# MCU_V3.net
KiCad netlist of a schematic drawn in EAGLE
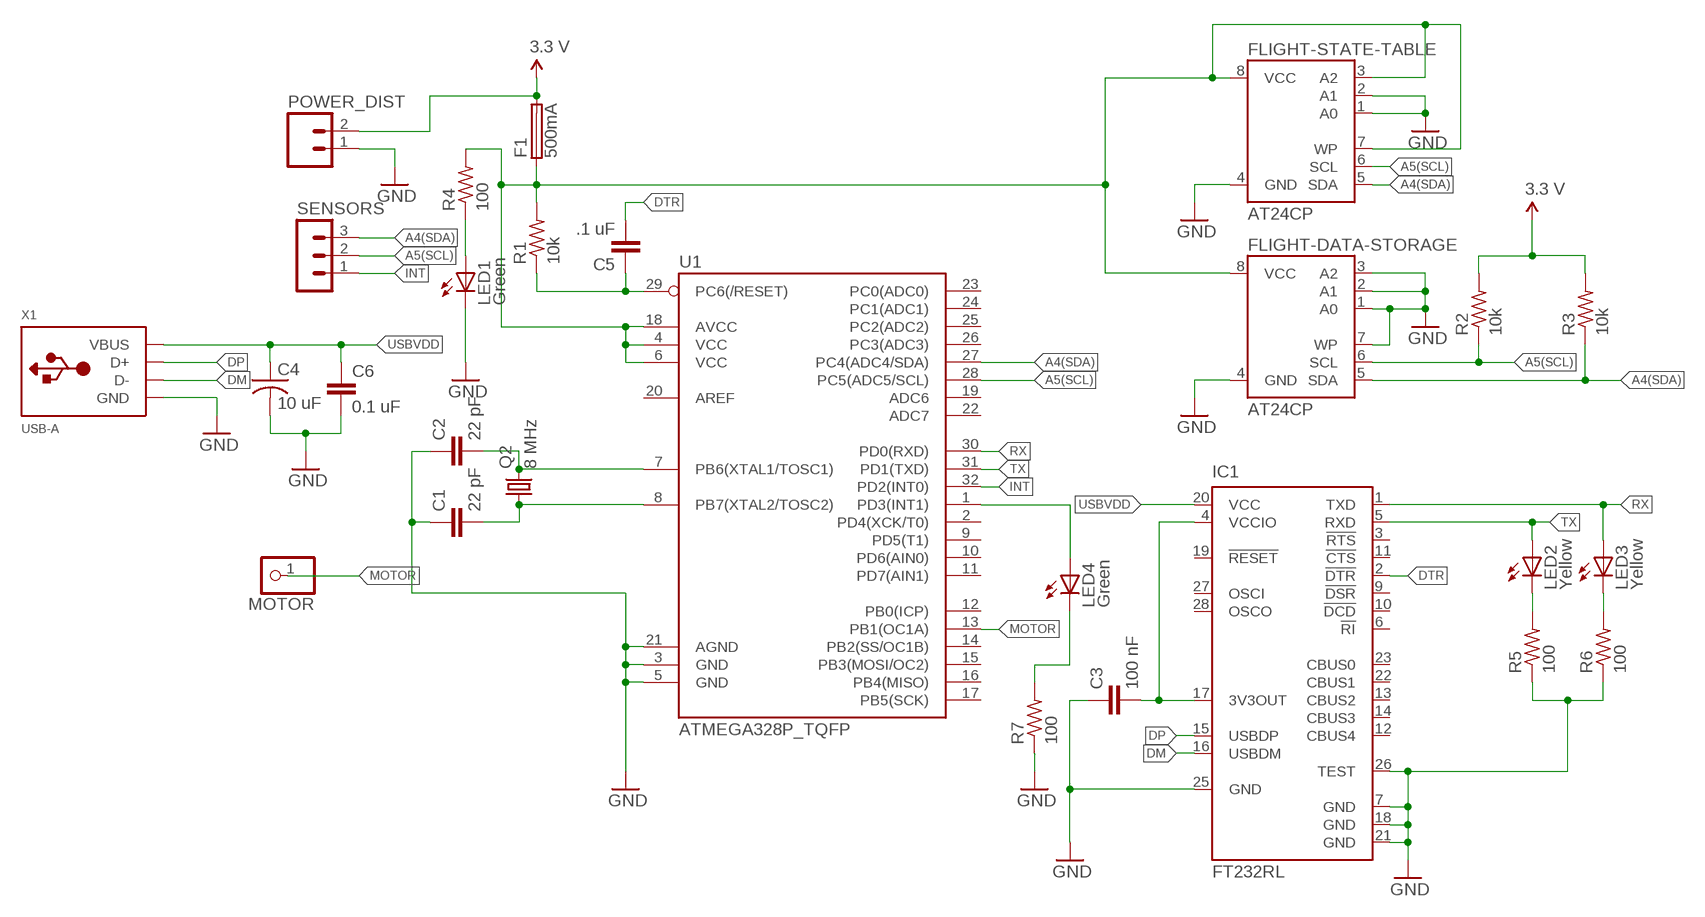
[diagram p0: schematic, sheet 1]

(export (version "E")
  (design (tool "Eeschema 10.0.6"))
  (components
    (comp (ref "C1")
      (value "22 pF")
      (footprint "eagle-import:C2.5-3")
      (libsource (lib "eagle-import") (part "C2,5-3"))
    )
    (comp (ref "C2")
      (value "22 pF")
      (footprint "eagle-import:C2.5-3")
      (libsource (lib "eagle-import") (part "C2,5-3"))
    )
    (comp (ref "C3")
      (value "100 nF")
      (footprint "eagle-import:C2.5-3")
      (libsource (lib "eagle-import") (part "C2,5-3"))
    )
    (comp (ref "C4")
      (value "10 uF")
      (footprint "eagle-import:C025-024X044")
      (libsource (lib "eagle-import") (part "C-US025-024X044"))
    )
    (comp (ref "C5")
      (value ".1 uF")
      (footprint "eagle-import:C2.5-3")
      (libsource (lib "eagle-import") (part "C2,5-3"))
    )
    (comp (ref "C6")
      (value "0.1 uF")
      (footprint "eagle-import:C2.5-3")
      (libsource (lib "eagle-import") (part "C2,5-3"))
    )
    (comp (ref "F1")
      (value "500mA")
      (footprint "eagle-import:PICOFUSE")
      (libsource (lib "eagle-import") (part "PICOFUSE"))
    )
    (comp (ref "FLIGHT-DATA-STORAGE")
      (value "AT24CP")
      (footprint "eagle-import:DIL08")
      (fields (field (name "MPN") "AT24C1024BW-SH-B"))
      (libsource (lib "eagle-import") (part "AT24CP"))
    )
    (comp (ref "FLIGHT-STATE-TABLE")
      (value "AT24CP")
      (footprint "eagle-import:DIL08")
      (fields (field (name "MPN") "AT24C1024BW-SH-B"))
      (libsource (lib "eagle-import") (part "AT24CP"))
    )
    (comp (ref "IC1")
      (value "FT232RL")
      (footprint "eagle-import:SSOP28")
      (libsource (lib "eagle-import") (part "FT232RL"))
    )
    (comp (ref "LED1")
      (value "Green")
      (footprint "eagle-import:LED_SML0603")
      (libsource (lib "eagle-import") (part "LED_ESML0603"))
    )
    (comp (ref "LED2")
      (value "Yellow")
      (footprint "eagle-import:LED_SML0603")
      (libsource (lib "eagle-import") (part "LED_ESML0603"))
    )
    (comp (ref "LED3")
      (value "Yellow")
      (footprint "eagle-import:LED_SML0603")
      (libsource (lib "eagle-import") (part "LED_ESML0603"))
    )
    (comp (ref "LED4")
      (value "Green")
      (footprint "eagle-import:LED_SML0603")
      (libsource (lib "eagle-import") (part "LED_ESML0603"))
    )
    (comp (ref "MOTOR")
      (value "PINHD-1X1")
      (footprint "eagle-import:1X01")
      (libsource (lib "eagle-import") (part "PINHD-1X1"))
    )
    (comp (ref "POWER_DIST")
      (value "M02PTH")
      (footprint "eagle-import:1X02")
      (libsource (lib "eagle-import") (part "M02PTH"))
    )
    (comp (ref "Q2")
      (value "8 MHz")
      (footprint "eagle-import:HC49_S")
      (libsource (lib "eagle-import") (part "CRYSTALHC49S"))
    )
    (comp (ref "R1")
      (value "10k")
      (footprint "eagle-import:R0805")
      (libsource (lib "eagle-import") (part "R-US_R0805"))
    )
    (comp (ref "R2")
      (value "10k")
      (footprint "eagle-import:R0805")
      (libsource (lib "eagle-import") (part "R-US_R0805"))
    )
    (comp (ref "R3")
      (value "10k")
      (footprint "eagle-import:R0805")
      (libsource (lib "eagle-import") (part "R-US_R0805"))
    )
    (comp (ref "R4")
      (value "100")
      (footprint "eagle-import:R0805")
      (libsource (lib "eagle-import") (part "R-US_R0805"))
    )
    (comp (ref "R5")
      (value "100")
      (footprint "eagle-import:R0805")
      (libsource (lib "eagle-import") (part "R-US_R0805"))
    )
    (comp (ref "R6")
      (value "100")
      (footprint "eagle-import:R0805")
      (libsource (lib "eagle-import") (part "R-US_R0805"))
    )
    (comp (ref "R7")
      (value "100")
      (footprint "eagle-import:R0805")
      (libsource (lib "eagle-import") (part "R-US_R0805"))
    )
    (comp (ref "SENSORS")
      (value "MA03-1")
      (footprint "eagle-import:MA03-1")
      (libsource (lib "eagle-import") (part "MA03-1"))
    )
    (comp (ref "U1")
      (value "ATMEGA328P_TQFP")
      (footprint "eagle-import:TQFP32-08")
      (libsource (lib "eagle-import") (part "ATMEGA328P_TQFP"))
    )
    (comp (ref "X1")
      (value "USB-A")
      (footprint "eagle-import:MOLEX_480371000")
      (libsource (lib "eagle-import") (part "USB-A"))
    )
  )
  (nets
    (net (code "1") (name "3.3 V") (class "Default")
      (node (ref "F1") (pin "2") (pinfunction "2_2") (pintype "passive"))
      (node (ref "POWER_DIST") (pin "2") (pinfunction "2_2") (pintype "passive"))
      (node (ref "R2") (pin "2") (pinfunction "2_2") (pintype "passive"))
      (node (ref "R3") (pin "2") (pinfunction "2_2") (pintype "passive"))
    )
    (net (code "2") (name "A4(SDA)") (class "Default")
      (node (ref "FLIGHT-DATA-STORAGE") (pin "5") (pinfunction "SDA_5") (pintype "bidirectional"))
      (node (ref "FLIGHT-STATE-TABLE") (pin "5") (pinfunction "SDA_5") (pintype "bidirectional"))
      (node (ref "R3") (pin "1") (pinfunction "1_1") (pintype "passive"))
      (node (ref "SENSORS") (pin "3") (pinfunction "3_3") (pintype "passive"))
      (node (ref "U1") (pin "27") (pinfunction "PC4(ADC4/SDA)_27") (pintype "bidirectional"))
    )
    (net (code "3") (name "A5(SCL)") (class "Default")
      (node (ref "FLIGHT-DATA-STORAGE") (pin "6") (pinfunction "SCL_6") (pintype "bidirectional"))
      (node (ref "FLIGHT-STATE-TABLE") (pin "6") (pinfunction "SCL_6") (pintype "bidirectional"))
      (node (ref "R2") (pin "1") (pinfunction "1_1") (pintype "passive"))
      (node (ref "SENSORS") (pin "2") (pinfunction "2_2") (pintype "passive"))
      (node (ref "U1") (pin "28") (pinfunction "PC5(ADC5/SCL)_28") (pintype "bidirectional"))
    )
    (net (code "4") (name "DM") (class "Default")
      (node (ref "IC1") (pin "16") (pinfunction "USBDM_16") (pintype "bidirectional"))
      (node (ref "X1") (pin "2") (pinfunction "D-_2") (pintype "bidirectional"))
    )
    (net (code "5") (name "DP") (class "Default")
      (node (ref "IC1") (pin "15") (pinfunction "USBDP_15") (pintype "bidirectional"))
      (node (ref "X1") (pin "3") (pinfunction "D+_3") (pintype "bidirectional"))
    )
    (net (code "6") (name "DTR") (class "Default")
      (node (ref "C5") (pin "2") (pinfunction "2_2") (pintype "passive"))
      (node (ref "IC1") (pin "2") (pinfunction "~{DTR}_2") (pintype "output"))
    )
    (net (code "7") (name "GND") (class "Default")
      (node (ref "C1") (pin "1") (pinfunction "1_1") (pintype "passive"))
      (node (ref "C2") (pin "1") (pinfunction "1_1") (pintype "passive"))
      (node (ref "C3") (pin "1") (pinfunction "1_1") (pintype "passive"))
      (node (ref "C4") (pin "2") (pinfunction "2_2") (pintype "passive"))
      (node (ref "C6") (pin "2") (pinfunction "2_2") (pintype "passive"))
      (node (ref "FLIGHT-DATA-STORAGE") (pin "1") (pinfunction "A0_1") (pintype "input"))
      (node (ref "FLIGHT-DATA-STORAGE") (pin "2") (pinfunction "A1_2") (pintype "input"))
      (node (ref "FLIGHT-DATA-STORAGE") (pin "3") (pinfunction "A2_3") (pintype "input"))
      (node (ref "FLIGHT-DATA-STORAGE") (pin "4") (pinfunction "GND_4") (pintype "power_in"))
      (node (ref "FLIGHT-DATA-STORAGE") (pin "7") (pinfunction "WP_7") (pintype "input"))
      (node (ref "FLIGHT-STATE-TABLE") (pin "1") (pinfunction "A0_1") (pintype "input"))
      (node (ref "FLIGHT-STATE-TABLE") (pin "2") (pinfunction "A1_2") (pintype "input"))
      (node (ref "FLIGHT-STATE-TABLE") (pin "4") (pinfunction "GND_4") (pintype "power_in"))
      (node (ref "IC1") (pin "18") (pinfunction "GND_18") (pintype "power_in"))
      (node (ref "IC1") (pin "21") (pinfunction "GND_21") (pintype "power_in"))
      (node (ref "IC1") (pin "25") (pinfunction "GND_25") (pintype "power_in"))
      (node (ref "IC1") (pin "26") (pinfunction "TEST_26") (pintype "input"))
      (node (ref "IC1") (pin "7") (pinfunction "GND_7") (pintype "power_in"))
      (node (ref "LED1") (pin "C") (pinfunction "C_C") (pintype "passive"))
      (node (ref "POWER_DIST") (pin "1") (pinfunction "1_1") (pintype "passive"))
      (node (ref "R5") (pin "1") (pinfunction "1_1") (pintype "passive"))
      (node (ref "R6") (pin "1") (pinfunction "1_1") (pintype "passive"))
      (node (ref "R7") (pin "1") (pinfunction "1_1") (pintype "passive"))
      (node (ref "U1") (pin "21") (pinfunction "AGND_21") (pintype "bidirectional"))
      (node (ref "U1") (pin "3") (pinfunction "GND_3") (pintype "bidirectional"))
      (node (ref "U1") (pin "5") (pinfunction "GND_5") (pintype "bidirectional"))
      (node (ref "X1") (pin "4") (pinfunction "GND_4") (pintype "power_in"))
    )
    (net (code "8") (name "INT") (class "Default")
      (node (ref "SENSORS") (pin "1") (pinfunction "1_1") (pintype "passive"))
      (node (ref "U1") (pin "32") (pinfunction "PD2(INT0)_32") (pintype "bidirectional"))
    )
    (net (code "9") (name "MOTOR") (class "Default")
      (node (ref "MOTOR") (pin "1") (pinfunction "1_1") (pintype "passive"))
      (node (ref "U1") (pin "13") (pinfunction "PB1(OC1A)_13") (pintype "bidirectional"))
    )
    (net (code "10") (name "Net-(FLIGHT-DATA-STORAGE-VCC)") (class "Default")
      (node (ref "F1") (pin "1") (pinfunction "1_1") (pintype "passive"))
      (node (ref "FLIGHT-DATA-STORAGE") (pin "8") (pinfunction "VCC_8") (pintype "power_in"))
      (node (ref "FLIGHT-STATE-TABLE") (pin "3") (pinfunction "A2_3") (pintype "input"))
      (node (ref "FLIGHT-STATE-TABLE") (pin "7") (pinfunction "WP_7") (pintype "input"))
      (node (ref "FLIGHT-STATE-TABLE") (pin "8") (pinfunction "VCC_8") (pintype "power_in"))
      (node (ref "R1") (pin "2") (pinfunction "2_2") (pintype "passive"))
      (node (ref "R4") (pin "2") (pinfunction "2_2") (pintype "passive"))
      (node (ref "U1") (pin "18") (pinfunction "AVCC_18") (pintype "bidirectional"))
      (node (ref "U1") (pin "4") (pinfunction "VCC_4") (pintype "bidirectional"))
      (node (ref "U1") (pin "6") (pinfunction "VCC_6") (pintype "bidirectional"))
    )
    (net (code "11") (name "Net-(IC1-3V3OUT)") (class "Default")
      (node (ref "C3") (pin "2") (pinfunction "2_2") (pintype "passive"))
      (node (ref "IC1") (pin "17") (pinfunction "3V3OUT_17") (pintype "output"))
      (node (ref "IC1") (pin "4") (pinfunction "VCCIO_4") (pintype "power_in"))
    )
    (net (code "12") (name "Net-(LED1-PadA)") (class "Default")
      (node (ref "LED1") (pin "A") (pinfunction "A_A") (pintype "passive"))
      (node (ref "R4") (pin "1") (pinfunction "1_1") (pintype "passive"))
    )
    (net (code "13") (name "Net-(LED2-PadC)") (class "Default")
      (node (ref "LED2") (pin "C") (pinfunction "C_C") (pintype "passive"))
      (node (ref "R5") (pin "2") (pinfunction "2_2") (pintype "passive"))
    )
    (net (code "14") (name "Net-(LED3-PadC)") (class "Default")
      (node (ref "LED3") (pin "C") (pinfunction "C_C") (pintype "passive"))
      (node (ref "R6") (pin "2") (pinfunction "2_2") (pintype "passive"))
    )
    (net (code "15") (name "Net-(LED4-PadC)") (class "Default")
      (node (ref "LED4") (pin "C") (pinfunction "C_C") (pintype "passive"))
      (node (ref "R7") (pin "2") (pinfunction "2_2") (pintype "passive"))
    )
    (net (code "16") (name "Net-(U1-PB6(XTAL1{slash}TOSC1))") (class "Default")
      (node (ref "C2") (pin "2") (pinfunction "2_2") (pintype "passive"))
      (node (ref "Q2") (pin "2") (pinfunction "2_2") (pintype "passive"))
      (node (ref "U1") (pin "7") (pinfunction "PB6(XTAL1/TOSC1)_7") (pintype "bidirectional"))
    )
    (net (code "17") (name "Net-(U1-PB7(XTAL2{slash}TOSC2))") (class "Default")
      (node (ref "C1") (pin "2") (pinfunction "2_2") (pintype "passive"))
      (node (ref "Q2") (pin "1") (pinfunction "1_1") (pintype "passive"))
      (node (ref "U1") (pin "8") (pinfunction "PB7(XTAL2/TOSC2)_8") (pintype "bidirectional"))
    )
    (net (code "18") (name "Net-(U1-PC6({slash}RESET))") (class "Default")
      (node (ref "C5") (pin "1") (pinfunction "1_1") (pintype "passive"))
      (node (ref "R1") (pin "1") (pinfunction "1_1") (pintype "passive"))
      (node (ref "U1") (pin "29") (pinfunction "PC6(/RESET)_29") (pintype "bidirectional"))
    )
    (net (code "19") (name "Net-(U1-PD3(INT1))") (class "Default")
      (node (ref "LED4") (pin "A") (pinfunction "A_A") (pintype "passive"))
      (node (ref "U1") (pin "1") (pinfunction "PD3(INT1)_1") (pintype "bidirectional"))
    )
    (net (code "20") (name "RX") (class "Default")
      (node (ref "IC1") (pin "1") (pinfunction "TXD_1") (pintype "output"))
      (node (ref "LED3") (pin "A") (pinfunction "A_A") (pintype "passive"))
      (node (ref "U1") (pin "30") (pinfunction "PD0(RXD)_30") (pintype "bidirectional"))
    )
    (net (code "21") (name "TX") (class "Default")
      (node (ref "IC1") (pin "5") (pinfunction "RXD_5") (pintype "input"))
      (node (ref "LED2") (pin "A") (pinfunction "A_A") (pintype "passive"))
      (node (ref "U1") (pin "31") (pinfunction "PD1(TXD)_31") (pintype "bidirectional"))
    )
    (net (code "22") (name "USBVDD") (class "Default")
      (node (ref "C4") (pin "1") (pinfunction "1_1") (pintype "passive"))
      (node (ref "C6") (pin "1") (pinfunction "1_1") (pintype "passive"))
      (node (ref "IC1") (pin "20") (pinfunction "VCC_20") (pintype "power_in"))
      (node (ref "X1") (pin "1") (pinfunction "VBUS_1") (pintype "power_in"))
    )
    (net (code "23") (name "unconnected-(IC1-CBUS0-Pad23)") (class "Default")
      (node (ref "IC1") (pin "23") (pinfunction "CBUS0_23") (pintype "bidirectional"))
    )
    (net (code "24") (name "unconnected-(IC1-CBUS1-Pad22)") (class "Default")
      (node (ref "IC1") (pin "22") (pinfunction "CBUS1_22") (pintype "bidirectional"))
    )
    (net (code "25") (name "unconnected-(IC1-CBUS2-Pad13)") (class "Default")
      (node (ref "IC1") (pin "13") (pinfunction "CBUS2_13") (pintype "bidirectional"))
    )
    (net (code "26") (name "unconnected-(IC1-CBUS3-Pad14)") (class "Default")
      (node (ref "IC1") (pin "14") (pinfunction "CBUS3_14") (pintype "bidirectional"))
    )
    (net (code "27") (name "unconnected-(IC1-CBUS4-Pad12)") (class "Default")
      (node (ref "IC1") (pin "12") (pinfunction "CBUS4_12") (pintype "bidirectional"))
    )
    (net (code "28") (name "unconnected-(IC1-OSCI-Pad27)") (class "Default")
      (node (ref "IC1") (pin "27") (pinfunction "OSCI_27") (pintype "input"))
    )
    (net (code "29") (name "unconnected-(IC1-OSCO-Pad28)") (class "Default")
      (node (ref "IC1") (pin "28") (pinfunction "OSCO_28") (pintype "output"))
    )
    (net (code "30") (name "unconnected-(IC1-~{CTS}-Pad11)") (class "Default")
      (node (ref "IC1") (pin "11") (pinfunction "~{CTS}_11") (pintype "input"))
    )
    (net (code "31") (name "unconnected-(IC1-~{DCD}-Pad10)") (class "Default")
      (node (ref "IC1") (pin "10") (pinfunction "~{DCD}_10") (pintype "input"))
    )
    (net (code "32") (name "unconnected-(IC1-~{DSR}-Pad9)") (class "Default")
      (node (ref "IC1") (pin "9") (pinfunction "~{DSR}_9") (pintype "input"))
    )
    (net (code "33") (name "unconnected-(IC1-~{RESET}-Pad19)") (class "Default")
      (node (ref "IC1") (pin "19") (pinfunction "~{RESET}_19") (pintype "input"))
    )
    (net (code "34") (name "unconnected-(IC1-~{RI}-Pad6)") (class "Default")
      (node (ref "IC1") (pin "6") (pinfunction "~{RI}_6") (pintype "input"))
    )
    (net (code "35") (name "unconnected-(IC1-~{RTS}-Pad3)") (class "Default")
      (node (ref "IC1") (pin "3") (pinfunction "~{RTS}_3") (pintype "output"))
    )
    (net (code "36") (name "unconnected-(U1-ADC6-Pad19)") (class "Default")
      (node (ref "U1") (pin "19") (pinfunction "ADC6_19") (pintype "bidirectional"))
    )
    (net (code "37") (name "unconnected-(U1-ADC7-Pad22)") (class "Default")
      (node (ref "U1") (pin "22") (pinfunction "ADC7_22") (pintype "bidirectional"))
    )
    (net (code "38") (name "unconnected-(U1-AREF-Pad20)") (class "Default")
      (node (ref "U1") (pin "20") (pinfunction "AREF_20") (pintype "bidirectional"))
    )
    (net (code "39") (name "unconnected-(U1-PB0(ICP)-Pad12)") (class "Default")
      (node (ref "U1") (pin "12") (pinfunction "PB0(ICP)_12") (pintype "bidirectional"))
    )
    (net (code "40") (name "unconnected-(U1-PB2(SS{slash}OC1B)-Pad14)") (class "Default")
      (node (ref "U1") (pin "14") (pinfunction "PB2(SS/OC1B)_14") (pintype "bidirectional"))
    )
    (net (code "41") (name "unconnected-(U1-PB3(MOSI{slash}OC2)-Pad15)") (class "Default")
      (node (ref "U1") (pin "15") (pinfunction "PB3(MOSI/OC2)_15") (pintype "bidirectional"))
    )
    (net (code "42") (name "unconnected-(U1-PB4(MISO)-Pad16)") (class "Default")
      (node (ref "U1") (pin "16") (pinfunction "PB4(MISO)_16") (pintype "bidirectional"))
    )
    (net (code "43") (name "unconnected-(U1-PB5(SCK)-Pad17)") (class "Default")
      (node (ref "U1") (pin "17") (pinfunction "PB5(SCK)_17") (pintype "bidirectional"))
    )
    (net (code "44") (name "unconnected-(U1-PC0(ADC0)-Pad23)") (class "Default")
      (node (ref "U1") (pin "23") (pinfunction "PC0(ADC0)_23") (pintype "bidirectional"))
    )
    (net (code "45") (name "unconnected-(U1-PC1(ADC1)-Pad24)") (class "Default")
      (node (ref "U1") (pin "24") (pinfunction "PC1(ADC1)_24") (pintype "bidirectional"))
    )
    (net (code "46") (name "unconnected-(U1-PC2(ADC2)-Pad25)") (class "Default")
      (node (ref "U1") (pin "25") (pinfunction "PC2(ADC2)_25") (pintype "bidirectional"))
    )
    (net (code "47") (name "unconnected-(U1-PC3(ADC3)-Pad26)") (class "Default")
      (node (ref "U1") (pin "26") (pinfunction "PC3(ADC3)_26") (pintype "bidirectional"))
    )
    (net (code "48") (name "unconnected-(U1-PD4(XCK{slash}T0)-Pad2)") (class "Default")
      (node (ref "U1") (pin "2") (pinfunction "PD4(XCK/T0)_2") (pintype "bidirectional"))
    )
    (net (code "49") (name "unconnected-(U1-PD5(T1)-Pad9)") (class "Default")
      (node (ref "U1") (pin "9") (pinfunction "PD5(T1)_9") (pintype "bidirectional"))
    )
    (net (code "50") (name "unconnected-(U1-PD6(AIN0)-Pad10)") (class "Default")
      (node (ref "U1") (pin "10") (pinfunction "PD6(AIN0)_10") (pintype "bidirectional"))
    )
    (net (code "51") (name "unconnected-(U1-PD7(AIN1)-Pad11)") (class "Default")
      (node (ref "U1") (pin "11") (pinfunction "PD7(AIN1)_11") (pintype "bidirectional"))
    )
  )
)
